# temp_sensor_ckt.net
KiCad netlist of a schematic drawn in EAGLE
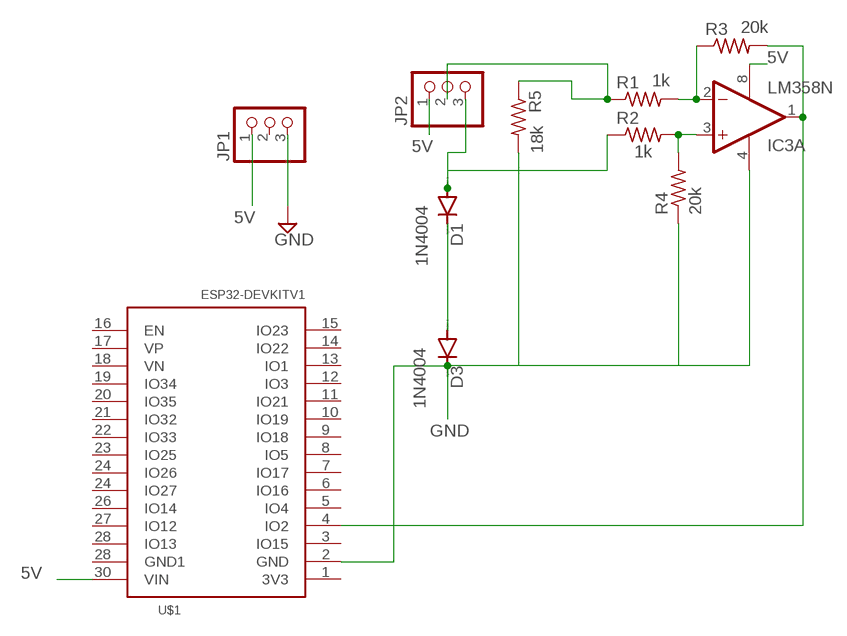
[diagram p0: schematic, sheet 1]

(export (version "E")
  (design (tool "Eeschema 10.0.6"))
  (components
    (comp (ref "D1")
      (value "1N4004")
      (footprint "eagle-import:DO41-10")
      (libsource (lib "eagle-import") (part "1N4004"))
    )
    (comp (ref "D3")
      (value "1N4004")
      (footprint "eagle-import:DO41-10")
      (libsource (lib "eagle-import") (part "1N4004"))
    )
    (comp (ref "IC3")
      (value "LM358N")
      (footprint "eagle-import:DIL08")
      (libsource (lib "eagle-import") (part "LM358N"))
    )
    (comp (ref "JP1")
      (value "PINHD-1X3")
      (footprint "eagle-import:1X03")
      (libsource (lib "eagle-import") (part "PINHD-1X3"))
    )
    (comp (ref "JP2")
      (value "PINHD-1X3")
      (footprint "eagle-import:1X03")
      (libsource (lib "eagle-import") (part "PINHD-1X3"))
    )
    (comp (ref "R1")
      (value "1k")
      (footprint "eagle-import:0207_10")
      (libsource (lib "eagle-import") (part "R-US_0207/10"))
    )
    (comp (ref "R2")
      (value "1k")
      (footprint "eagle-import:0207_10")
      (libsource (lib "eagle-import") (part "R-US_0207/10"))
    )
    (comp (ref "R3")
      (value "20k")
      (footprint "eagle-import:0207_10")
      (libsource (lib "eagle-import") (part "R-US_0207/10"))
    )
    (comp (ref "R4")
      (value "20k")
      (footprint "eagle-import:0207_10")
      (libsource (lib "eagle-import") (part "R-US_0207/10"))
    )
    (comp (ref "R5")
      (value "18k")
      (footprint "eagle-import:0207_10")
      (libsource (lib "eagle-import") (part "R-US_0207/10"))
    )
    (comp (ref "U$1")
      (value "ESP32DEVKITV1")
      (footprint "eagle-import:ESP32-DEVKITV1")
      (libsource (lib "eagle-import") (part "ESP32DEVKITV1"))
    )
  )
  (nets
    (net (code "1") (name "/5V") (class "Default")
      (node (ref "IC3") (pin "8") (pinfunction "V+_8") (pintype "power_in"))
      (node (ref "JP1") (pin "1") (pinfunction "1_1") (pintype "passive"))
      (node (ref "JP2") (pin "1") (pinfunction "1_1") (pintype "passive"))
      (node (ref "U$1") (pin "30") (pinfunction "VIN_30") (pintype "bidirectional"))
    )
    (net (code "2") (name "GND") (class "Default")
      (node (ref "D3") (pin "C") (pinfunction "C_C") (pintype "passive"))
      (node (ref "IC3") (pin "4") (pinfunction "V-_4") (pintype "power_in"))
      (node (ref "JP1") (pin "3") (pinfunction "3_3") (pintype "passive"))
      (node (ref "R4") (pin "1") (pinfunction "1_1") (pintype "passive"))
      (node (ref "R5") (pin "2") (pinfunction "2_2") (pintype "passive"))
      (node (ref "U$1") (pin "2") (pinfunction "GND_2") (pintype "bidirectional"))
    )
    (net (code "3") (name "Net-(D1-PadA)") (class "Default")
      (node (ref "D1") (pin "A") (pinfunction "A_A") (pintype "passive"))
      (node (ref "JP2") (pin "3") (pinfunction "3_3") (pintype "passive"))
      (node (ref "R2") (pin "1") (pinfunction "1_1") (pintype "passive"))
    )
    (net (code "4") (name "Net-(D1-PadC)") (class "Default")
      (node (ref "D1") (pin "C") (pinfunction "C_C") (pintype "passive"))
      (node (ref "D3") (pin "A") (pinfunction "A_A") (pintype "passive"))
    )
    (net (code "5") (name "Net-(IC3A-+IN)") (class "Default")
      (node (ref "IC3") (pin "3") (pinfunction "+IN_3") (pintype "input"))
      (node (ref "R2") (pin "2") (pinfunction "2_2") (pintype "passive"))
      (node (ref "R4") (pin "2") (pinfunction "2_2") (pintype "passive"))
    )
    (net (code "6") (name "Net-(IC3A--IN)") (class "Default")
      (node (ref "IC3") (pin "2") (pinfunction "-IN_2") (pintype "input"))
      (node (ref "R1") (pin "2") (pinfunction "2_2") (pintype "passive"))
      (node (ref "R3") (pin "1") (pinfunction "1_1") (pintype "passive"))
    )
    (net (code "7") (name "Net-(IC3A-OUT)") (class "Default")
      (node (ref "IC3") (pin "1") (pinfunction "OUT_1") (pintype "output"))
      (node (ref "R3") (pin "2") (pinfunction "2_2") (pintype "passive"))
      (node (ref "U$1") (pin "4") (pinfunction "IO2_4") (pintype "bidirectional"))
    )
    (net (code "8") (name "Net-(JP2-Pad2)") (class "Default")
      (node (ref "JP2") (pin "2") (pinfunction "2_2") (pintype "passive"))
      (node (ref "R1") (pin "1") (pinfunction "1_1") (pintype "passive"))
      (node (ref "R5") (pin "1") (pinfunction "1_1") (pintype "passive"))
    )
    (net (code "9") (name "unconnected-(JP1-Pad2)") (class "Default")
      (node (ref "JP1") (pin "2") (pinfunction "2_2") (pintype "passive"))
    )
    (net (code "10") (name "unconnected-(U$1-3V3-Pad1)") (class "Default")
      (node (ref "U$1") (pin "1") (pinfunction "3V3_1") (pintype "bidirectional"))
    )
    (net (code "11") (name "unconnected-(U$1-EN-Pad16)") (class "Default")
      (node (ref "U$1") (pin "16") (pinfunction "EN_16") (pintype "bidirectional"))
    )
    (net (code "12") (name "unconnected-(U$1-GND1-Pad28)") (class "Default")
      (node (ref "U$1") (pin "28") (pinfunction "GND1_28") (pintype "bidirectional"))
    )
    (net (code "13") (name "unconnected-(U$1-IO1-Pad13)") (class "Default")
      (node (ref "U$1") (pin "13") (pinfunction "IO1_13") (pintype "bidirectional"))
    )
    (net (code "14") (name "unconnected-(U$1-IO3-Pad12)") (class "Default")
      (node (ref "U$1") (pin "12") (pinfunction "IO3_12") (pintype "bidirectional"))
    )
    (net (code "15") (name "unconnected-(U$1-IO4-Pad5)") (class "Default")
      (node (ref "U$1") (pin "5") (pinfunction "IO4_5") (pintype "bidirectional"))
    )
    (net (code "16") (name "unconnected-(U$1-IO5-Pad8)") (class "Default")
      (node (ref "U$1") (pin "8") (pinfunction "IO5_8") (pintype "bidirectional"))
    )
    (net (code "17") (name "unconnected-(U$1-IO12-Pad27)") (class "Default")
      (node (ref "U$1") (pin "27") (pinfunction "IO12_27") (pintype "bidirectional"))
    )
    (net (code "18") (name "unconnected-(U$1-IO13-Pad28)") (class "Default")
      (node (ref "U$1") (pin "28") (pinfunction "IO13_28") (pintype "bidirectional"))
    )
    (net (code "19") (name "unconnected-(U$1-IO14-Pad26)") (class "Default")
      (node (ref "U$1") (pin "26") (pinfunction "IO14_26") (pintype "bidirectional"))
    )
    (net (code "20") (name "unconnected-(U$1-IO15-Pad3)") (class "Default")
      (node (ref "U$1") (pin "3") (pinfunction "IO15_3") (pintype "bidirectional"))
    )
    (net (code "21") (name "unconnected-(U$1-IO16-Pad6)") (class "Default")
      (node (ref "U$1") (pin "6") (pinfunction "IO16_6") (pintype "bidirectional"))
    )
    (net (code "22") (name "unconnected-(U$1-IO17-Pad7)") (class "Default")
      (node (ref "U$1") (pin "7") (pinfunction "IO17_7") (pintype "bidirectional"))
    )
    (net (code "23") (name "unconnected-(U$1-IO18-Pad9)") (class "Default")
      (node (ref "U$1") (pin "9") (pinfunction "IO18_9") (pintype "bidirectional"))
    )
    (net (code "24") (name "unconnected-(U$1-IO19-Pad10)") (class "Default")
      (node (ref "U$1") (pin "10") (pinfunction "IO19_10") (pintype "bidirectional"))
    )
    (net (code "25") (name "unconnected-(U$1-IO21-Pad11)") (class "Default")
      (node (ref "U$1") (pin "11") (pinfunction "IO21_11") (pintype "bidirectional"))
    )
    (net (code "26") (name "unconnected-(U$1-IO22-Pad14)") (class "Default")
      (node (ref "U$1") (pin "14") (pinfunction "IO22_14") (pintype "bidirectional"))
    )
    (net (code "27") (name "unconnected-(U$1-IO23-Pad15)") (class "Default")
      (node (ref "U$1") (pin "15") (pinfunction "IO23_15") (pintype "bidirectional"))
    )
    (net (code "28") (name "unconnected-(U$1-IO25-Pad23)") (class "Default")
      (node (ref "U$1") (pin "23") (pinfunction "IO25_23") (pintype "bidirectional"))
    )
    (net (code "29") (name "unconnected-(U$1-IO26-Pad24)") (class "Default")
      (node (ref "U$1") (pin "24") (pinfunction "IO26_24") (pintype "bidirectional"))
    )
    (net (code "30") (name "unconnected-(U$1-IO27-Pad24)") (class "Default")
      (node (ref "U$1") (pin "24") (pinfunction "IO27_24") (pintype "bidirectional"))
    )
    (net (code "31") (name "unconnected-(U$1-IO32-Pad21)") (class "Default")
      (node (ref "U$1") (pin "21") (pinfunction "IO32_21") (pintype "bidirectional"))
    )
    (net (code "32") (name "unconnected-(U$1-IO33-Pad22)") (class "Default")
      (node (ref "U$1") (pin "22") (pinfunction "IO33_22") (pintype "bidirectional"))
    )
    (net (code "33") (name "unconnected-(U$1-IO34-Pad19)") (class "Default")
      (node (ref "U$1") (pin "19") (pinfunction "IO34_19") (pintype "bidirectional"))
    )
    (net (code "34") (name "unconnected-(U$1-IO35-Pad20)") (class "Default")
      (node (ref "U$1") (pin "20") (pinfunction "IO35_20") (pintype "bidirectional"))
    )
    (net (code "35") (name "unconnected-(U$1-VN-Pad18)") (class "Default")
      (node (ref "U$1") (pin "18") (pinfunction "VN_18") (pintype "bidirectional"))
    )
    (net (code "36") (name "unconnected-(U$1-VP-Pad17)") (class "Default")
      (node (ref "U$1") (pin "17") (pinfunction "VP_17") (pintype "bidirectional"))
    )
  )
)
